# braslet_pcb.net
KiCad netlist of a schematic drawn in Altium Designer
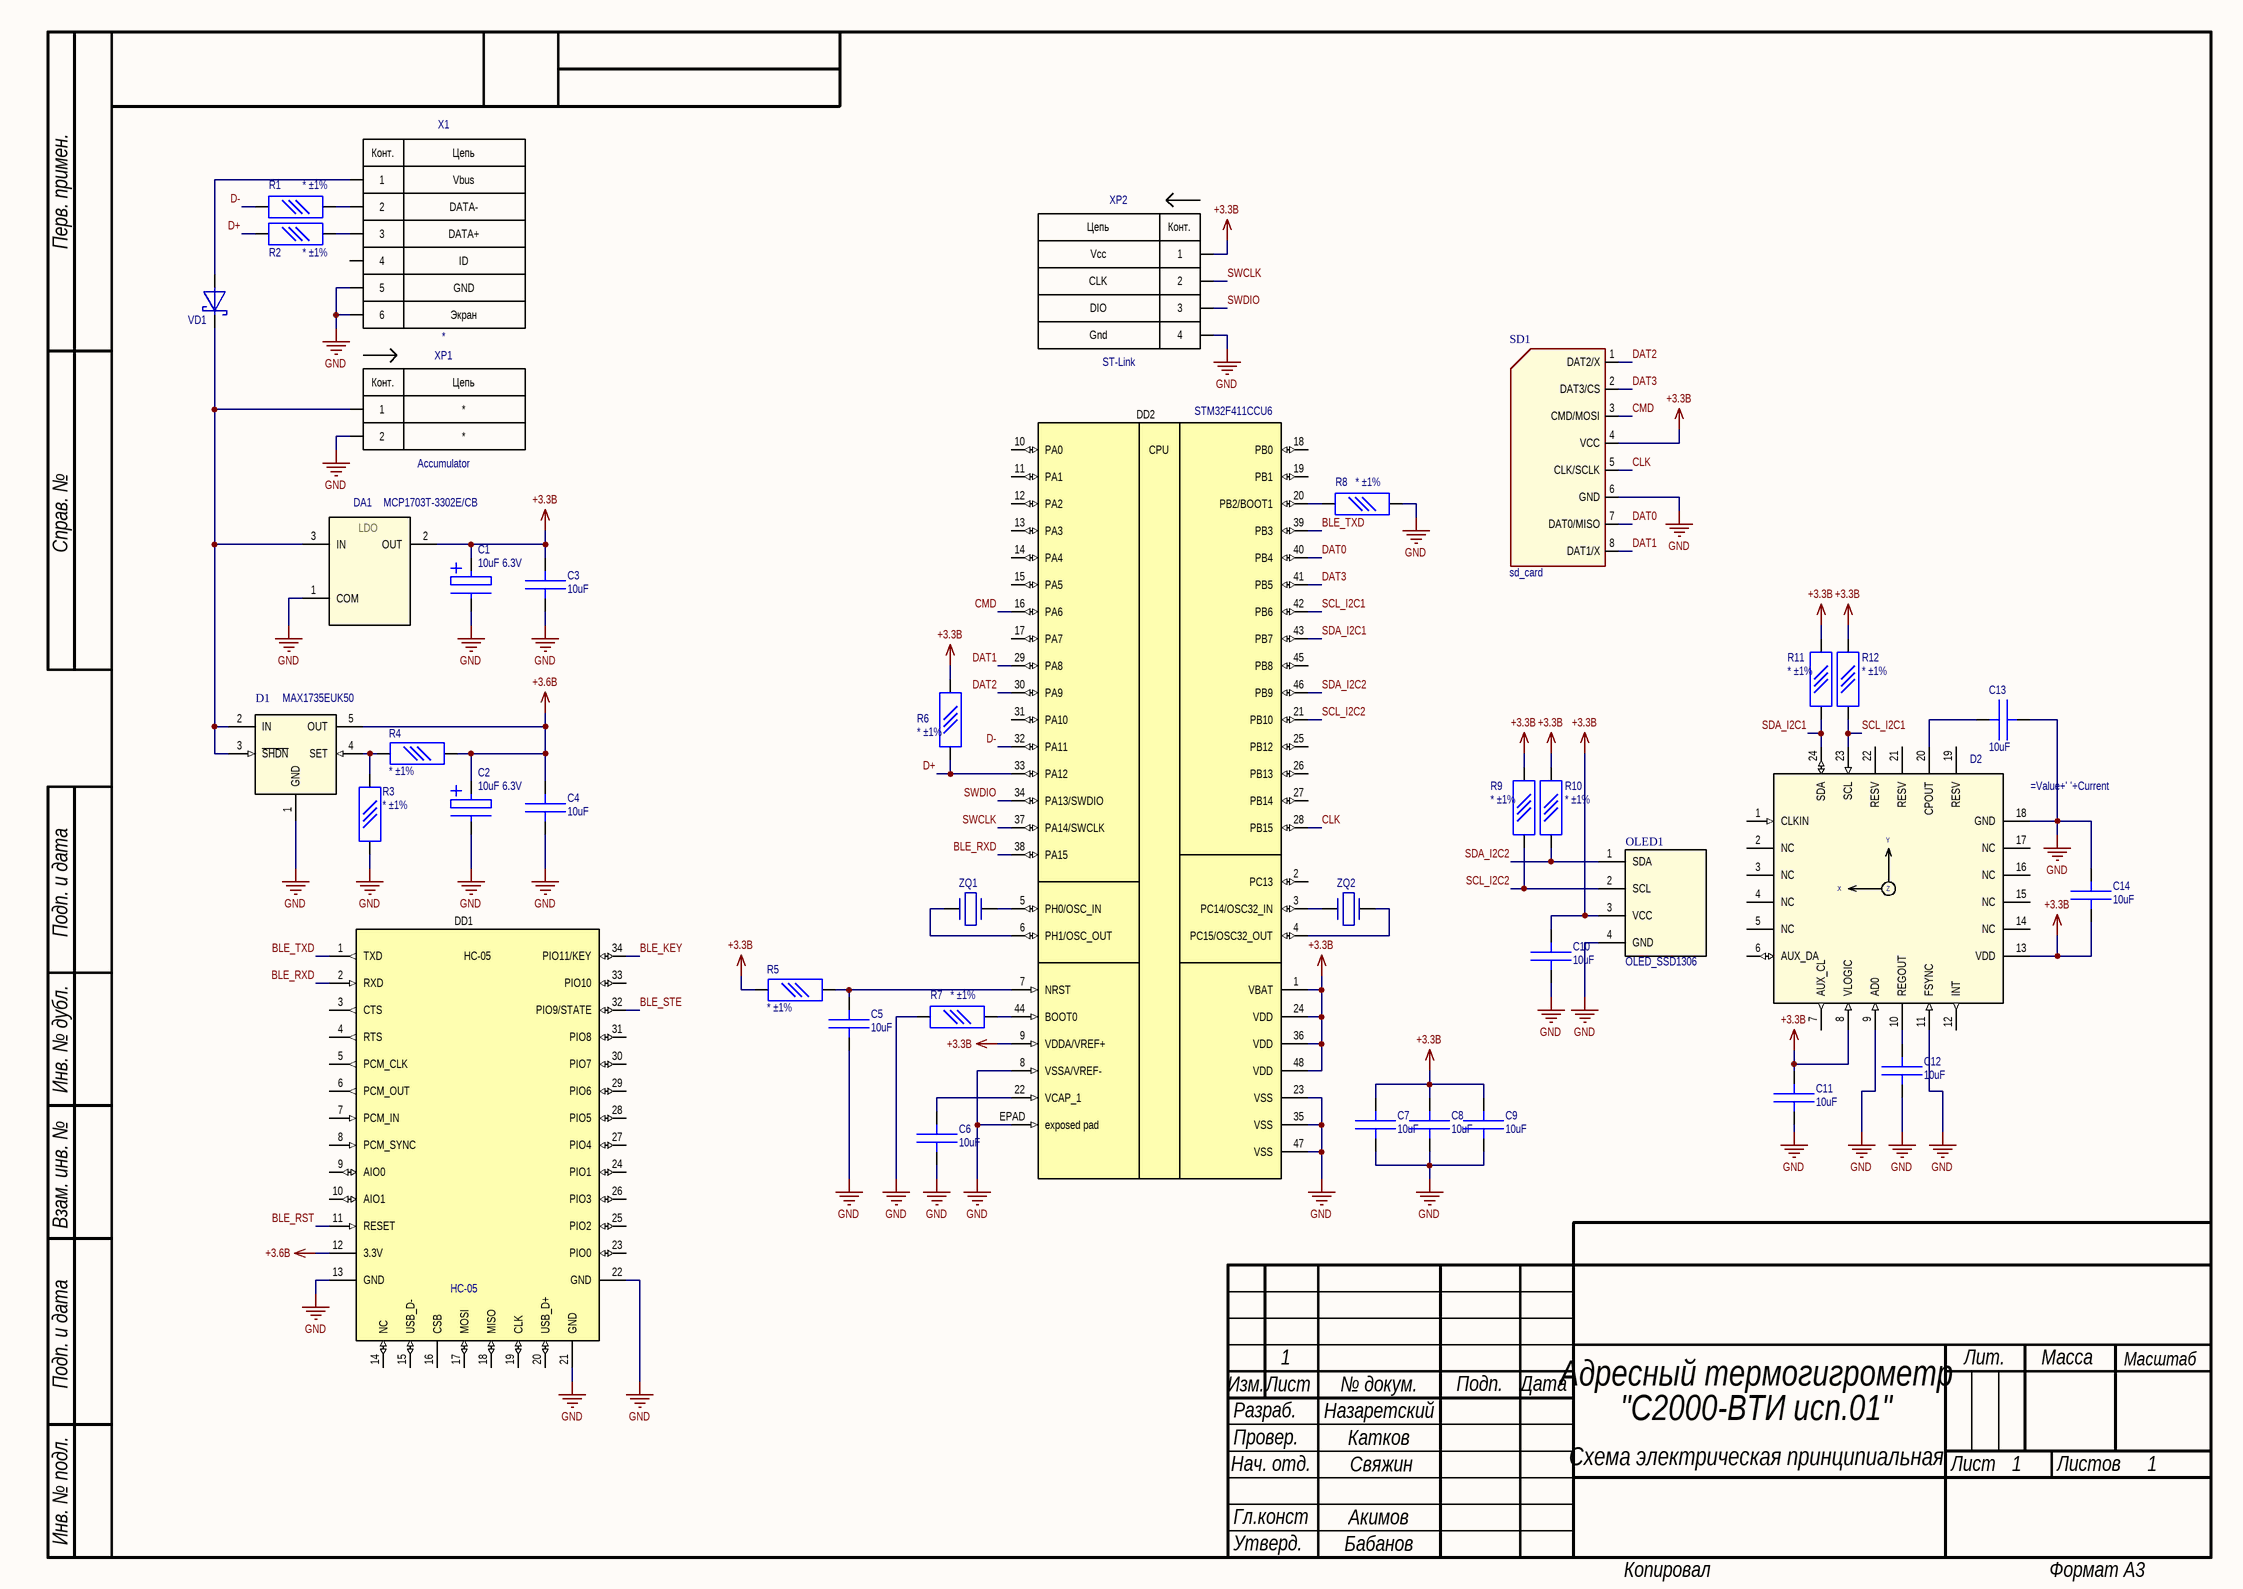
[diagram p0: braslet_pcb.SchDoc]

(export (version "E")
  (design (tool "Eeschema 10.0.6"))
  (components
    (comp (ref "C1")
      (value "10uF 6.3V")
      (footprint "TANT_3.2X1.6_A")
      (description "Конденсатор SMD CC 3216-10uF-10%-6,3V (Case A)  Vishay (AVX)")
      (fields
        (field (name "PART NUMBER") "3216-10uF-10%-6,3V")
        (field (name "VOLTAGE") "6.3V")
        (field (name "CREATOR") "Турнаев С.С.")
      )
      (libsource (lib "BolidLib1") (part "Capacitor_polar"))
    )
    (comp (ref "C2")
      (value "10uF 6.3V")
      (footprint "TANT_3.2X1.6_A")
      (description "Конденсатор SMD CC 3216-10uF-10%-6,3V (Case A)  Vishay (AVX)")
      (fields
        (field (name "PART NUMBER") "3216-10uF-10%-6,3V")
        (field (name "VOLTAGE") "6.3V")
        (field (name "CREATOR") "Турнаев С.С.")
      )
      (libsource (lib "BolidLib1") (part "Capacitor_polar"))
    )
    (comp (ref "C3")
      (value "10uF")
      (footprint "CC0603_0.8mm")
      (description "Конденсатор SMD CC 0603-X5R-10uF-20%-6,3V CL10A106MQ8NNNC SAMSUNG")
      (fields (field (name "PART NUMBER") "C0603_X5R_10uF_20%_6.3V") (field (name "VOLTAGE") "6.3V"))
      (libsource (lib "BolidLib1") (part "Capacitor"))
    )
    (comp (ref "C4")
      (value "10uF")
      (footprint "CC0603_0.8mm")
      (description "Конденсатор SMD CC 0603-X5R-10uF-20%-6,3V CL10A106MQ8NNNC SAMSUNG")
      (fields (field (name "PART NUMBER") "C0603_X5R_10uF_20%_6.3V") (field (name "VOLTAGE") "6.3V"))
      (libsource (lib "BolidLib1") (part "Capacitor"))
    )
    (comp (ref "C5")
      (value "10uF")
      (footprint "CC0603_0.8mm")
      (description "Конденсатор SMD CC 0603-X5R-10uF-20%-6,3V CL10A106MQ8NNNC SAMSUNG")
      (fields (field (name "PART NUMBER") "C0603_X5R_10uF_20%_6.3V") (field (name "VOLTAGE") "6.3V"))
      (libsource (lib "BolidLib1") (part "Capacitor"))
    )
    (comp (ref "C6")
      (value "10uF")
      (footprint "CC0603_0.8mm")
      (description "Конденсатор SMD CC 0603-X5R-10uF-20%-6,3V CL10A106MQ8NNNC SAMSUNG")
      (fields (field (name "PART NUMBER") "C0603_X5R_10uF_20%_6.3V") (field (name "VOLTAGE") "6.3V"))
      (libsource (lib "BolidLib1") (part "Capacitor"))
    )
    (comp (ref "C7")
      (value "10uF")
      (footprint "CC0603_0.8mm")
      (description "Конденсатор SMD CC 0603-X5R-10uF-20%-6,3V CL10A106MQ8NNNC SAMSUNG")
      (fields (field (name "PART NUMBER") "C0603_X5R_10uF_20%_6.3V") (field (name "VOLTAGE") "6.3V"))
      (libsource (lib "BolidLib1") (part "Capacitor"))
    )
    (comp (ref "C8")
      (value "10uF")
      (footprint "CC0603_0.8mm")
      (description "Конденсатор SMD CC 0603-X5R-10uF-20%-6,3V CL10A106MQ8NNNC SAMSUNG")
      (fields (field (name "PART NUMBER") "C0603_X5R_10uF_20%_6.3V") (field (name "VOLTAGE") "6.3V"))
      (libsource (lib "BolidLib1") (part "Capacitor"))
    )
    (comp (ref "C9")
      (value "10uF")
      (footprint "CC0603_0.8mm")
      (description "Конденсатор SMD CC 0603-X5R-10uF-20%-6,3V CL10A106MQ8NNNC SAMSUNG")
      (fields (field (name "PART NUMBER") "C0603_X5R_10uF_20%_6.3V") (field (name "VOLTAGE") "6.3V"))
      (libsource (lib "BolidLib1") (part "Capacitor"))
    )
    (comp (ref "C10")
      (value "10uF")
      (footprint "CC0603_0.8mm")
      (description "Конденсатор SMD CC 0603-X5R-10uF-20%-6,3V CL10A106MQ8NNNC SAMSUNG")
      (fields (field (name "PART NUMBER") "C0603_X5R_10uF_20%_6.3V") (field (name "VOLTAGE") "6.3V"))
      (libsource (lib "BolidLib1") (part "Capacitor"))
    )
    (comp (ref "C11")
      (value "10uF")
      (footprint "CC0603_0.8mm")
      (description "Конденсатор SMD CC 0603-X5R-10uF-20%-6,3V CL10A106MQ8NNNC SAMSUNG")
      (fields (field (name "PART NUMBER") "C0603_X5R_10uF_20%_6.3V") (field (name "VOLTAGE") "6.3V"))
      (libsource (lib "BolidLib1") (part "Capacitor"))
    )
    (comp (ref "C12")
      (value "10uF")
      (footprint "CC0603_0.8mm")
      (description "Конденсатор SMD CC 0603-X5R-10uF-20%-6,3V CL10A106MQ8NNNC SAMSUNG")
      (fields (field (name "PART NUMBER") "C0603_X5R_10uF_20%_6.3V") (field (name "VOLTAGE") "6.3V"))
      (libsource (lib "BolidLib1") (part "Capacitor"))
    )
    (comp (ref "C13")
      (value "10uF")
      (footprint "CC0603_0.8mm")
      (description "Конденсатор SMD CC 0603-X5R-10uF-20%-6,3V CL10A106MQ8NNNC SAMSUNG")
      (fields (field (name "PART NUMBER") "C0603_X5R_10uF_20%_6.3V") (field (name "VOLTAGE") "6.3V"))
      (libsource (lib "BolidLib1") (part "Capacitor"))
    )
    (comp (ref "C14")
      (value "10uF")
      (footprint "CC0603_0.8mm")
      (description "Конденсатор SMD CC 0603-X5R-10uF-20%-6,3V CL10A106MQ8NNNC SAMSUNG")
      (fields (field (name "PART NUMBER") "C0603_X5R_10uF_20%_6.3V") (field (name "VOLTAGE") "6.3V"))
      (libsource (lib "BolidLib1") (part "Capacitor"))
    )
    (comp (ref "D1")
      (value "MAX1735EUK50")
      (footprint "SOT-23-5")
      (libsource (lib "AD_lib") (part "MAX1735EUK50"))
    )
    (comp (ref "D2") (value "~") (footprint "QFN24_4X4mm") (libsource (lib "AD_lib") (part "ADXL327")))
    (comp (ref "DA1")
      (value "MCP1703T-3302E/CB")
      (footprint "SOT-23A_MCP")
      (libsource (lib "AD_lib") (part "MCP1703T-3302E/CB"))
    )
    (comp (ref "DD1")
      (value "HC-05")
      (footprint "HC-05")
      (description "Bluetooth module")
      (libsource (lib "AD_lib") (part "HC-05"))
    )
    (comp (ref "DD2")
      (value "STM32F411CCU6")
      (footprint "UFQFPN48_7x7_STM")
      (description "ARM-based 32-bit MCU")
      (libsource (lib "AD_lib") (part "STM32F411CCU6"))
    )
    (comp (ref "OLED1")
      (value "OLED_SSD1306")
      (footprint "oled_128x32")
      (libsource (lib "AD_lib") (part "OLED_SSD1306"))
    )
    (comp (ref "R1")
      (value "* ±1%")
      (footprint "R0603")
      (fields (field (name "TOLERANCE") "±1%"))
      (libsource (lib "AD_lib") (part "Res_0603"))
    )
    (comp (ref "R2")
      (value "* ±1%")
      (footprint "R0603")
      (fields (field (name "TOLERANCE") "±1%"))
      (libsource (lib "AD_lib") (part "Res_0603"))
    )
    (comp (ref "R3")
      (value "* ±1%")
      (footprint "R0603")
      (fields (field (name "TOLERANCE") "±1%"))
      (libsource (lib "AD_lib") (part "Res_0603"))
    )
    (comp (ref "R4")
      (value "* ±1%")
      (footprint "R0603")
      (fields (field (name "TOLERANCE") "±1%"))
      (libsource (lib "AD_lib") (part "Res_0603"))
    )
    (comp (ref "R5")
      (value "* ±1%")
      (footprint "R0603")
      (fields (field (name "TOLERANCE") "±1%"))
      (libsource (lib "AD_lib") (part "Res_0603"))
    )
    (comp (ref "R6")
      (value "* ±1%")
      (footprint "R0603")
      (fields (field (name "TOLERANCE") "±1%"))
      (libsource (lib "AD_lib") (part "Res_0603"))
    )
    (comp (ref "R7")
      (value "* ±1%")
      (footprint "R0603")
      (fields (field (name "TOLERANCE") "±1%"))
      (libsource (lib "AD_lib") (part "Res_0603"))
    )
    (comp (ref "R8")
      (value "* ±1%")
      (footprint "R0603")
      (fields (field (name "TOLERANCE") "±1%"))
      (libsource (lib "AD_lib") (part "Res_0603"))
    )
    (comp (ref "R9")
      (value "* ±1%")
      (footprint "R0603")
      (fields (field (name "TOLERANCE") "±1%"))
      (libsource (lib "AD_lib") (part "Res_0603"))
    )
    (comp (ref "R10")
      (value "* ±1%")
      (footprint "R0603")
      (fields (field (name "TOLERANCE") "±1%"))
      (libsource (lib "AD_lib") (part "Res_0603"))
    )
    (comp (ref "R11")
      (value "* ±1%")
      (footprint "R0603")
      (fields (field (name "TOLERANCE") "±1%"))
      (libsource (lib "AD_lib") (part "Res_0603"))
    )
    (comp (ref "R12")
      (value "* ±1%")
      (footprint "R0603")
      (fields (field (name "TOLERANCE") "±1%"))
      (libsource (lib "AD_lib") (part "Res_0603"))
    )
    (comp (ref "SD1") (value "sd_card") (footprint "sd_conn") (libsource (lib "AD_lib") (part "sd_card")))
    (comp (ref "VD1")
      (value "MBR0530T3G.1G")
      (footprint "SOD-123")
      (description "Диод Шоттки SMD MBR0530T3G.1G")
      (fields (field (name "MANUFACTURER") "Fairchild") (field (name "CREATOR") "Турнаев С.С."))
      (libsource (lib "BolidLib1") (part "Schottky"))
    )
    (comp (ref "X1")
      (value "*")
      (footprint "MICRO-USB-B (629105136821)")
      (fields
        (field (name "CIRCUIT_1") "Vbus")
        (field (name "CIRCUIT_2") "DATA-")
        (field (name "CIRCUIT_3") "DATA+")
        (field (name "CIRCUIT_4") "GND")
        (field (name "CIRCUIT_5") "ID")
      )
      (libsource (lib "AD_lib") (part "USB_5pin"))
    )
    (comp (ref "XP1")
      (value "Accumulator")
      (footprint "Conn_01x02")
      (fields (field (name "CIRCUIT_1") "*") (field (name "CIRCUIT_2") "*"))
      (libsource (lib "AD_lib") (part "Conn_01x02"))
    )
    (comp (ref "XP2")
      (value "ST-Link")
      (footprint "B4B-ZR")
      (fields
        (field (name "CIRCUIT_1") "Vcc")
        (field (name "CIRCUIT_2") "CLK")
        (field (name "CIRCUIT_3") "DIO")
        (field (name "CIRCUIT_4") "Gnd")
      )
      (libsource (lib "AD_lib") (part "B4B-ZR_conn_01x04_st_link"))
    )
    (comp (ref "ZQ1")
      (value "~")
      (footprint "NX3225GD")
      (description "Резонатор кварцевый SMD NX3225GD-8MHz STD-CRA-3")
      (fields (field (name "PART NUMBER") "NX3225GD-8MHz STD") (field (name "CREATOR") "Назаретский С.А."))
      (libsource (lib "BolidLib1") (part "XTAL"))
    )
    (comp (ref "ZQ2")
      (value "~")
      (footprint "NX3225GD")
      (description "Резонатор кварцевый SMD NX3225GD-8MHz STD-CRA-3")
      (fields (field (name "PART NUMBER") "NX3225GD-8MHz STD") (field (name "CREATOR") "Назаретский С.А."))
      (libsource (lib "BolidLib1") (part "XTAL"))
    )
  )
  (nets
    (net (code "1") (name "+3.3B") (class "Default")
      (node (ref "C1") (pin "2") (pinfunction "+_2") (pintype "passive"))
      (node (ref "C10") (pin "1") (pintype "passive"))
      (node (ref "C11") (pin "1") (pintype "passive"))
      (node (ref "C14") (pin "2") (pintype "passive"))
      (node (ref "C3") (pin "1") (pintype "passive"))
      (node (ref "C7") (pin "1") (pintype "passive"))
      (node (ref "C8") (pin "1") (pintype "passive"))
      (node (ref "C9") (pin "1") (pintype "passive"))
      (node (ref "D2") (pin "13") (pinfunction "VDD_13") (pintype "power_in"))
      (node (ref "D2") (pin "8") (pinfunction "VLOGIC_8") (pintype "input"))
      (node (ref "DA1") (pin "2") (pinfunction "OUT_2") (pintype "passive"))
      (node (ref "DD2") (pin "1") (pinfunction "VBAT_1") (pintype "power_in"))
      (node (ref "DD2") (pin "24") (pinfunction "VDD_24") (pintype "power_in"))
      (node (ref "DD2") (pin "36") (pinfunction "VDD_36") (pintype "power_in"))
      (node (ref "DD2") (pin "48") (pinfunction "VDD_48") (pintype "power_in"))
      (node (ref "DD2") (pin "9") (pinfunction "VDDA/VREF+_9") (pintype "input"))
      (node (ref "OLED1") (pin "3") (pinfunction "VCC_3") (pintype "passive"))
      (node (ref "R10") (pin "2") (pinfunction "TOP_2") (pintype "passive"))
      (node (ref "R11") (pin "2") (pinfunction "TOP_2") (pintype "passive"))
      (node (ref "R12") (pin "2") (pinfunction "TOP_2") (pintype "passive"))
      (node (ref "R5") (pin "2") (pinfunction "TOP_2") (pintype "passive"))
      (node (ref "R6") (pin "2") (pinfunction "TOP_2") (pintype "passive"))
      (node (ref "R9") (pin "2") (pinfunction "TOP_2") (pintype "passive"))
      (node (ref "SD1") (pin "4") (pinfunction "VCC_4") (pintype "passive"))
      (node (ref "XP2") (pin "1") (pinfunction "1_1") (pintype "passive"))
    )
    (net (code "2") (name "+3.6B") (class "Default")
      (node (ref "C2") (pin "2") (pinfunction "+_2") (pintype "passive"))
      (node (ref "C4") (pin "1") (pintype "passive"))
      (node (ref "D1") (pin "5") (pinfunction "OUT_5") (pintype "power_in"))
      (node (ref "DD1") (pin "12") (pinfunction "3.3V_12") (pintype "power_in"))
      (node (ref "R4") (pin "2") (pinfunction "TOP_2") (pintype "passive"))
    )
    (net (code "3") (name "/BLE_KEY") (class "Default")
      (node (ref "DD1") (pin "34") (pinfunction "PIO11/KEY_34") (pintype "bidirectional"))
    )
    (net (code "4") (name "/BLE_RST") (class "Default")
      (node (ref "DD1") (pin "11") (pinfunction "RESET_11") (pintype "input"))
    )
    (net (code "5") (name "/BLE_RXD") (class "Default")
      (node (ref "DD1") (pin "2") (pinfunction "RXD_2") (pintype "input"))
      (node (ref "DD2") (pin "38") (pinfunction "PA15_38") (pintype "bidirectional"))
    )
    (net (code "6") (name "/BLE_STE") (class "Default")
      (node (ref "DD1") (pin "32") (pinfunction "PIO9/STATE_32") (pintype "bidirectional"))
    )
    (net (code "7") (name "/BLE_TXD") (class "Default")
      (node (ref "DD1") (pin "1") (pinfunction "TXD_1") (pintype "output"))
      (node (ref "DD2") (pin "39") (pinfunction "PB3_39") (pintype "bidirectional"))
    )
    (net (code "8") (name "/CLK") (class "Default")
      (node (ref "DD2") (pin "28") (pinfunction "PB15_28") (pintype "bidirectional"))
      (node (ref "SD1") (pin "5") (pinfunction "CLK/SCLK_5") (pintype "passive"))
    )
    (net (code "9") (name "/CMD") (class "Default")
      (node (ref "DD2") (pin "16") (pinfunction "PA6_16") (pintype "bidirectional"))
      (node (ref "SD1") (pin "3") (pinfunction "CMD/MOSI_3") (pintype "passive"))
    )
    (net (code "10") (name "/D+") (class "Default")
      (node (ref "DD2") (pin "33") (pinfunction "PA12_33") (pintype "bidirectional"))
      (node (ref "R2") (pin "1") (pinfunction "BOT_1") (pintype "passive"))
      (node (ref "R6") (pin "1") (pinfunction "BOT_1") (pintype "passive"))
    )
    (net (code "11") (name "/D-") (class "Default")
      (node (ref "DD2") (pin "32") (pinfunction "PA11_32") (pintype "bidirectional"))
      (node (ref "R1") (pin "1") (pinfunction "BOT_1") (pintype "passive"))
    )
    (net (code "12") (name "/DAT0") (class "Default")
      (node (ref "DD2") (pin "40") (pinfunction "PB4_40") (pintype "bidirectional"))
      (node (ref "SD1") (pin "7") (pinfunction "DAT0/MISO_7") (pintype "passive"))
    )
    (net (code "13") (name "/DAT1") (class "Default")
      (node (ref "DD2") (pin "29") (pinfunction "PA8_29") (pintype "bidirectional"))
      (node (ref "SD1") (pin "8") (pinfunction "DAT1/X_8") (pintype "passive"))
    )
    (net (code "14") (name "/DAT2") (class "Default")
      (node (ref "DD2") (pin "30") (pinfunction "PA9_30") (pintype "bidirectional"))
      (node (ref "SD1") (pin "1") (pinfunction "DAT2/X_1") (pintype "passive"))
    )
    (net (code "15") (name "/DAT3") (class "Default")
      (node (ref "DD2") (pin "41") (pinfunction "PB5_41") (pintype "bidirectional"))
      (node (ref "SD1") (pin "2") (pinfunction "DAT3/CS_2") (pintype "passive"))
    )
    (net (code "16") (name "/SCL_I2C1") (class "Default")
      (node (ref "D2") (pin "23") (pinfunction "SCL_23") (pintype "input"))
      (node (ref "DD2") (pin "42") (pinfunction "PB6_42") (pintype "bidirectional"))
      (node (ref "R12") (pin "1") (pinfunction "BOT_1") (pintype "passive"))
    )
    (net (code "17") (name "/SCL_I2C2") (class "Default")
      (node (ref "DD2") (pin "21") (pinfunction "PB10_21") (pintype "bidirectional"))
      (node (ref "OLED1") (pin "2") (pinfunction "SCL_2") (pintype "passive"))
      (node (ref "R9") (pin "1") (pinfunction "BOT_1") (pintype "passive"))
    )
    (net (code "18") (name "/SDA_I2C1") (class "Default")
      (node (ref "D2") (pin "24") (pinfunction "SDA_24") (pintype "bidirectional"))
      (node (ref "DD2") (pin "43") (pinfunction "PB7_43") (pintype "bidirectional"))
      (node (ref "R11") (pin "1") (pinfunction "BOT_1") (pintype "passive"))
    )
    (net (code "19") (name "/SDA_I2C2") (class "Default")
      (node (ref "DD2") (pin "46") (pinfunction "PB9_46") (pintype "bidirectional"))
      (node (ref "OLED1") (pin "1") (pinfunction "SDA_1") (pintype "passive"))
      (node (ref "R10") (pin "1") (pinfunction "BOT_1") (pintype "passive"))
    )
    (net (code "20") (name "/SWCLK") (class "Default")
      (node (ref "DD2") (pin "37") (pinfunction "PA14/SWCLK_37") (pintype "bidirectional"))
      (node (ref "XP2") (pin "2") (pinfunction "2_2") (pintype "passive"))
    )
    (net (code "21") (name "/SWDIO") (class "Default")
      (node (ref "DD2") (pin "34") (pinfunction "PA13/SWDIO_34") (pintype "bidirectional"))
      (node (ref "XP2") (pin "3") (pinfunction "3_3") (pintype "passive"))
    )
    (net (code "22") (name "GND") (class "Default")
      (node (ref "C1") (pin "1") (pinfunction "-_1") (pintype "passive"))
      (node (ref "C10") (pin "2") (pintype "passive"))
      (node (ref "C11") (pin "2") (pintype "passive"))
      (node (ref "C12") (pin "2") (pintype "passive"))
      (node (ref "C13") (pin "2") (pintype "passive"))
      (node (ref "C14") (pin "1") (pintype "passive"))
      (node (ref "C2") (pin "1") (pinfunction "-_1") (pintype "passive"))
      (node (ref "C3") (pin "2") (pintype "passive"))
      (node (ref "C4") (pin "2") (pintype "passive"))
      (node (ref "C5") (pin "2") (pintype "passive"))
      (node (ref "C6") (pin "2") (pintype "passive"))
      (node (ref "C7") (pin "2") (pintype "passive"))
      (node (ref "C8") (pin "2") (pintype "passive"))
      (node (ref "C9") (pin "2") (pintype "passive"))
      (node (ref "D1") (pin "1") (pinfunction "GND_1") (pintype "power_in"))
      (node (ref "D2") (pin "11") (pinfunction "FSYNC_11") (pintype "input"))
      (node (ref "D2") (pin "18") (pinfunction "GND_18") (pintype "power_in"))
      (node (ref "D2") (pin "9") (pinfunction "AD0_9") (pintype "input"))
      (node (ref "DA1") (pin "1") (pinfunction "COM_1") (pintype "passive"))
      (node (ref "DD1") (pin "13") (pinfunction "GND_13") (pintype "power_in"))
      (node (ref "DD1") (pin "21") (pinfunction "GND_21") (pintype "power_in"))
      (node (ref "DD1") (pin "22") (pinfunction "GND_22") (pintype "power_in"))
      (node (ref "DD2") (pin "23") (pinfunction "VSS_23") (pintype "power_in"))
      (node (ref "DD2") (pin "35") (pinfunction "VSS_35") (pintype "power_in"))
      (node (ref "DD2") (pin "47") (pinfunction "VSS_47") (pintype "power_in"))
      (node (ref "DD2") (pin "8") (pinfunction "VSSA/VREF-_8") (pintype "input"))
      (node (ref "DD2") (pin "EPAD") (pinfunction "exposed_pad_EPAD") (pintype "input"))
      (node (ref "OLED1") (pin "4") (pinfunction "GND_4") (pintype "passive"))
      (node (ref "R3") (pin "1") (pinfunction "BOT_1") (pintype "passive"))
      (node (ref "R7") (pin "2") (pinfunction "TOP_2") (pintype "passive"))
      (node (ref "R8") (pin "1") (pinfunction "BOT_1") (pintype "passive"))
      (node (ref "SD1") (pin "6") (pinfunction "GND_6") (pintype "passive"))
      (node (ref "X1") (pin "5") (pinfunction "5_5") (pintype "passive"))
      (node (ref "X1") (pin "Shield") (pinfunction "6_Shield") (pintype "passive"))
      (node (ref "XP1") (pin "2") (pinfunction "2_2") (pintype "passive"))
      (node (ref "XP2") (pin "4") (pinfunction "4_4") (pintype "passive"))
    )
    (net (code "23") (name "Net-(D1-IN)") (class "Default")
      (node (ref "D1") (pin "2") (pinfunction "IN_2") (pintype "power_in"))
      (node (ref "D1") (pin "3") (pinfunction "~{SHDN}_3") (pintype "input"))
      (node (ref "DA1") (pin "3") (pinfunction "IN_3") (pintype "passive"))
      (node (ref "VD1") (pin "1") (pinfunction "C_1") (pintype "passive"))
      (node (ref "XP1") (pin "1") (pinfunction "1_1") (pintype "passive"))
    )
    (net (code "24") (name "Net-(D1-SET)") (class "Default")
      (node (ref "D1") (pin "4") (pinfunction "SET_4") (pintype "input"))
      (node (ref "R3") (pin "2") (pinfunction "TOP_2") (pintype "passive"))
      (node (ref "R4") (pin "1") (pinfunction "BOT_1") (pintype "passive"))
    )
    (net (code "25") (name "Net-(D2-CPOUT)") (class "Default")
      (node (ref "C13") (pin "1") (pintype "passive"))
      (node (ref "D2") (pin "20") (pinfunction "CPOUT_20") (pintype "power_in"))
    )
    (net (code "26") (name "Net-(D2-REGOUT)") (class "Default")
      (node (ref "C12") (pin "1") (pintype "passive"))
      (node (ref "D2") (pin "10") (pinfunction "REGOUT_10") (pintype "power_in"))
    )
    (net (code "27") (name "Net-(DD2-BOOT0)") (class "Default")
      (node (ref "DD2") (pin "44") (pinfunction "BOOT0_44") (pintype "input"))
      (node (ref "R7") (pin "1") (pinfunction "BOT_1") (pintype "passive"))
    )
    (net (code "28") (name "Net-(DD2-NRST)") (class "Default")
      (node (ref "C5") (pin "1") (pintype "passive"))
      (node (ref "DD2") (pin "7") (pinfunction "NRST_7") (pintype "input"))
      (node (ref "R5") (pin "1") (pinfunction "BOT_1") (pintype "passive"))
    )
    (net (code "29") (name "Net-(DD2-PB2{slash}BOOT1)") (class "Default")
      (node (ref "DD2") (pin "20") (pinfunction "PB2/BOOT1_20") (pintype "bidirectional"))
      (node (ref "R8") (pin "2") (pinfunction "TOP_2") (pintype "passive"))
    )
    (net (code "30") (name "Net-(DD2-PC14{slash}OSC32_IN)") (class "Default")
      (node (ref "DD2") (pin "3") (pinfunction "PC14/OSC32_IN_3") (pintype "bidirectional"))
      (node (ref "ZQ2") (pin "1") (pinfunction "1_1") (pintype "passive"))
    )
    (net (code "31") (name "Net-(DD2-PC15{slash}OSC32_OUT)") (class "Default")
      (node (ref "DD2") (pin "4") (pinfunction "PC15/OSC32_OUT_4") (pintype "bidirectional"))
      (node (ref "ZQ2") (pin "2") (pinfunction "2_2") (pintype "passive"))
    )
    (net (code "32") (name "Net-(DD2-PH0{slash}OSC_IN)") (class "Default")
      (node (ref "DD2") (pin "5") (pinfunction "PH0/OSC_IN_5") (pintype "bidirectional"))
      (node (ref "ZQ1") (pin "2") (pinfunction "2_2") (pintype "passive"))
    )
    (net (code "33") (name "Net-(DD2-PH1{slash}OSC_OUT)") (class "Default")
      (node (ref "DD2") (pin "6") (pinfunction "PH1/OSC_OUT_6") (pintype "bidirectional"))
      (node (ref "ZQ1") (pin "1") (pinfunction "1_1") (pintype "passive"))
    )
    (net (code "34") (name "Net-(DD2-VCAP_1)") (class "Default")
      (node (ref "C6") (pin "1") (pintype "passive"))
      (node (ref "DD2") (pin "22") (pinfunction "VCAP_1_22") (pintype "input"))
    )
    (net (code "35") (name "Net-(R1-TOP)") (class "Default")
      (node (ref "R1") (pin "2") (pinfunction "TOP_2") (pintype "passive"))
      (node (ref "X1") (pin "2") (pinfunction "2_2") (pintype "passive"))
    )
    (net (code "36") (name "Net-(R2-TOP)") (class "Default")
      (node (ref "R2") (pin "2") (pinfunction "TOP_2") (pintype "passive"))
      (node (ref "X1") (pin "3") (pinfunction "3_3") (pintype "passive"))
    )
    (net (code "37") (name "Net-(VD1-A)") (class "Default")
      (node (ref "VD1") (pin "2") (pinfunction "A_2") (pintype "passive"))
      (node (ref "X1") (pin "1") (pinfunction "1_1") (pintype "passive"))
    )
    (net (code "38") (name "unconnected-(D2-AUX_CL-Pad7)") (class "Default")
      (node (ref "D2") (pin "7") (pinfunction "AUX_CL_7") (pintype "output"))
    )
    (net (code "39") (name "unconnected-(D2-AUX_DA-Pad6)") (class "Default")
      (node (ref "D2") (pin "6") (pinfunction "AUX_DA_6") (pintype "bidirectional"))
    )
    (net (code "40") (name "unconnected-(D2-CLKIN-Pad1)") (class "Default")
      (node (ref "D2") (pin "1") (pinfunction "CLKIN_1") (pintype "input"))
    )
    (net (code "41") (name "unconnected-(D2-INT-Pad12)") (class "Default")
      (node (ref "D2") (pin "12") (pinfunction "INT_12") (pintype "output"))
    )
    (net (code "42") (name "unconnected-(D2-NC-Pad2)") (class "Default")
      (node (ref "D2") (pin "2") (pinfunction "NC_2") (pintype "passive"))
    )
    (net (code "43") (name "unconnected-(D2-NC-Pad3)") (class "Default")
      (node (ref "D2") (pin "3") (pinfunction "NC_3") (pintype "passive"))
    )
    (net (code "44") (name "unconnected-(D2-NC-Pad4)") (class "Default")
      (node (ref "D2") (pin "4") (pinfunction "NC_4") (pintype "passive"))
    )
    (net (code "45") (name "unconnected-(D2-NC-Pad5)") (class "Default")
      (node (ref "D2") (pin "5") (pinfunction "NC_5") (pintype "passive"))
    )
    (net (code "46") (name "unconnected-(D2-NC-Pad14)") (class "Default")
      (node (ref "D2") (pin "14") (pinfunction "NC_14") (pintype "passive"))
    )
    (net (code "47") (name "unconnected-(D2-NC-Pad15)") (class "Default")
      (node (ref "D2") (pin "15") (pinfunction "NC_15") (pintype "passive"))
    )
    (net (code "48") (name "unconnected-(D2-NC-Pad16)") (class "Default")
      (node (ref "D2") (pin "16") (pinfunction "NC_16") (pintype "passive"))
    )
    (net (code "49") (name "unconnected-(D2-NC-Pad17)") (class "Default")
      (node (ref "D2") (pin "17") (pinfunction "NC_17") (pintype "passive"))
    )
    (net (code "50") (name "unconnected-(D2-RESV-Pad19)") (class "Default")
      (node (ref "D2") (pin "19") (pinfunction "RESV_19") (pintype "passive"))
    )
    (net (code "51") (name "unconnected-(D2-RESV-Pad21)") (class "Default")
      (node (ref "D2") (pin "21") (pinfunction "RESV_21") (pintype "passive"))
    )
    (net (code "52") (name "unconnected-(D2-RESV-Pad22)") (class "Default")
      (node (ref "D2") (pin "22") (pinfunction "RESV_22") (pintype "passive"))
    )
    (net (code "53") (name "unconnected-(DD1-AIO0-Pad9)") (class "Default")
      (node (ref "DD1") (pin "9") (pinfunction "AIO0_9") (pintype "bidirectional"))
    )
    (net (code "54") (name "unconnected-(DD1-AIO1-Pad10)") (class "Default")
      (node (ref "DD1") (pin "10") (pinfunction "AIO1_10") (pintype "bidirectional"))
    )
    (net (code "55") (name "unconnected-(DD1-CLK-Pad19)") (class "Default")
      (node (ref "DD1") (pin "19") (pinfunction "CLK_19") (pintype "bidirectional"))
    )
    (net (code "56") (name "unconnected-(DD1-CSB-Pad16)") (class "Default")
      (node (ref "DD1") (pin "16") (pinfunction "CSB_16") (pintype "power_in"))
    )
    (net (code "57") (name "unconnected-(DD1-CTS-Pad3)") (class "Default")
      (node (ref "DD1") (pin "3") (pinfunction "CTS_3") (pintype "output"))
    )
    (net (code "58") (name "unconnected-(DD1-MISO-Pad18)") (class "Default")
      (node (ref "DD1") (pin "18") (pinfunction "MISO_18") (pintype "bidirectional"))
    )
    (net (code "59") (name "unconnected-(DD1-MOSI-Pad17)") (class "Default")
      (node (ref "DD1") (pin "17") (pinfunction "MOSI_17") (pintype "bidirectional"))
    )
    (net (code "60") (name "unconnected-(DD1-NC-Pad14)") (class "Default")
      (node (ref "DD1") (pin "14") (pinfunction "NC_14") (pintype "bidirectional"))
    )
    (net (code "61") (name "unconnected-(DD1-PCM_CLK-Pad5)") (class "Default")
      (node (ref "DD1") (pin "5") (pinfunction "PCM_CLK_5") (pintype "output"))
    )
    (net (code "62") (name "unconnected-(DD1-PCM_IN-Pad7)") (class "Default")
      (node (ref "DD1") (pin "7") (pinfunction "PCM_IN_7") (pintype "input"))
    )
    (net (code "63") (name "unconnected-(DD1-PCM_OUT-Pad6)") (class "Default")
      (node (ref "DD1") (pin "6") (pinfunction "PCM_OUT_6") (pintype "output"))
    )
    (net (code "64") (name "unconnected-(DD1-PCM_SYNC-Pad8)") (class "Default")
      (node (ref "DD1") (pin "8") (pinfunction "PCM_SYNC_8") (pintype "input"))
    )
    (net (code "65") (name "unconnected-(DD1-PIO0-Pad23)") (class "Default")
      (node (ref "DD1") (pin "23") (pinfunction "PIO0_23") (pintype "bidirectional"))
    )
    (net (code "66") (name "unconnected-(DD1-PIO1-Pad24)") (class "Default")
      (node (ref "DD1") (pin "24") (pinfunction "PIO1_24") (pintype "bidirectional"))
    )
    (net (code "67") (name "unconnected-(DD1-PIO2-Pad25)") (class "Default")
      (node (ref "DD1") (pin "25") (pinfunction "PIO2_25") (pintype "bidirectional"))
    )
    (net (code "68") (name "unconnected-(DD1-PIO3-Pad26)") (class "Default")
      (node (ref "DD1") (pin "26") (pinfunction "PIO3_26") (pintype "bidirectional"))
    )
    (net (code "69") (name "unconnected-(DD1-PIO4-Pad27)") (class "Default")
      (node (ref "DD1") (pin "27") (pinfunction "PIO4_27") (pintype "bidirectional"))
    )
    (net (code "70") (name "unconnected-(DD1-PIO5-Pad28)") (class "Default")
      (node (ref "DD1") (pin "28") (pinfunction "PIO5_28") (pintype "bidirectional"))
    )
    (net (code "71") (name "unconnected-(DD1-PIO6-Pad29)") (class "Default")
      (node (ref "DD1") (pin "29") (pinfunction "PIO6_29") (pintype "bidirectional"))
    )
    (net (code "72") (name "unconnected-(DD1-PIO7-Pad30)") (class "Default")
      (node (ref "DD1") (pin "30") (pinfunction "PIO7_30") (pintype "bidirectional"))
    )
    (net (code "73") (name "unconnected-(DD1-PIO8-Pad31)") (class "Default")
      (node (ref "DD1") (pin "31") (pinfunction "PIO8_31") (pintype "bidirectional"))
    )
    (net (code "74") (name "unconnected-(DD1-PIO10-Pad33)") (class "Default")
      (node (ref "DD1") (pin "33") (pinfunction "PIO10_33") (pintype "bidirectional"))
    )
    (net (code "75") (name "unconnected-(DD1-RTS-Pad4)") (class "Default")
      (node (ref "DD1") (pin "4") (pinfunction "RTS_4") (pintype "output"))
    )
    (net (code "76") (name "unconnected-(DD1-USB_D+-Pad20)") (class "Default")
      (node (ref "DD1") (pin "20") (pinfunction "USB_D+_20") (pintype "bidirectional"))
    )
    (net (code "77") (name "unconnected-(DD1-USB_D--Pad15)") (class "Default")
      (node (ref "DD1") (pin "15") (pinfunction "USB_D-_15") (pintype "bidirectional"))
    )
    (net (code "78") (name "unconnected-(DD2-PA0-Pad10)") (class "Default")
      (node (ref "DD2") (pin "10") (pinfunction "PA0_10") (pintype "bidirectional"))
    )
    (net (code "79") (name "unconnected-(DD2-PA1-Pad11)") (class "Default")
      (node (ref "DD2") (pin "11") (pinfunction "PA1_11") (pintype "bidirectional"))
    )
    (net (code "80") (name "unconnected-(DD2-PA2-Pad12)") (class "Default")
      (node (ref "DD2") (pin "12") (pinfunction "PA2_12") (pintype "bidirectional"))
    )
    (net (code "81") (name "unconnected-(DD2-PA3-Pad13)") (class "Default")
      (node (ref "DD2") (pin "13") (pinfunction "PA3_13") (pintype "bidirectional"))
    )
    (net (code "82") (name "unconnected-(DD2-PA4-Pad14)") (class "Default")
      (node (ref "DD2") (pin "14") (pinfunction "PA4_14") (pintype "bidirectional"))
    )
    (net (code "83") (name "unconnected-(DD2-PA5-Pad15)") (class "Default")
      (node (ref "DD2") (pin "15") (pinfunction "PA5_15") (pintype "bidirectional"))
    )
    (net (code "84") (name "unconnected-(DD2-PA7-Pad17)") (class "Default")
      (node (ref "DD2") (pin "17") (pinfunction "PA7_17") (pintype "bidirectional"))
    )
    (net (code "85") (name "unconnected-(DD2-PA10-Pad31)") (class "Default")
      (node (ref "DD2") (pin "31") (pinfunction "PA10_31") (pintype "bidirectional"))
    )
    (net (code "86") (name "unconnected-(DD2-PB0-Pad18)") (class "Default")
      (node (ref "DD2") (pin "18") (pinfunction "PB0_18") (pintype "bidirectional"))
    )
    (net (code "87") (name "unconnected-(DD2-PB1-Pad19)") (class "Default")
      (node (ref "DD2") (pin "19") (pinfunction "PB1_19") (pintype "bidirectional"))
    )
    (net (code "88") (name "unconnected-(DD2-PB8-Pad45)") (class "Default")
      (node (ref "DD2") (pin "45") (pinfunction "PB8_45") (pintype "bidirectional"))
    )
    (net (code "89") (name "unconnected-(DD2-PB12-Pad25)") (class "Default")
      (node (ref "DD2") (pin "25") (pinfunction "PB12_25") (pintype "bidirectional"))
    )
    (net (code "90") (name "unconnected-(DD2-PB13-Pad26)") (class "Default")
      (node (ref "DD2") (pin "26") (pinfunction "PB13_26") (pintype "bidirectional"))
    )
    (net (code "91") (name "unconnected-(DD2-PB14-Pad27)") (class "Default")
      (node (ref "DD2") (pin "27") (pinfunction "PB14_27") (pintype "bidirectional"))
    )
    (net (code "92") (name "unconnected-(DD2-PC13-Pad2)") (class "Default")
      (node (ref "DD2") (pin "2") (pinfunction "PC13_2") (pintype "bidirectional"))
    )
    (net (code "93") (name "unconnected-(X1-Pad4)") (class "Default")
      (node (ref "X1") (pin "4") (pinfunction "4_4") (pintype "passive"))
    )
  )
)
